# sensor_de_linha.net
KiCad netlist of a schematic drawn in EAGLE
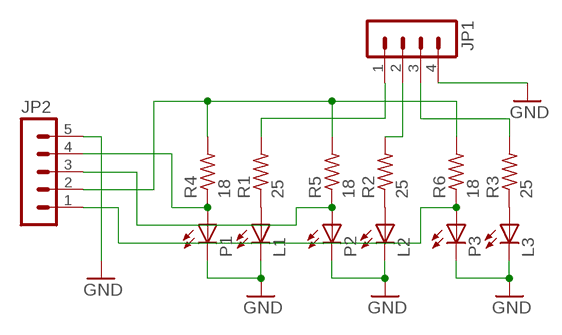
[diagram p0: schematic, sheet 1]

(export (version "E")
  (design (tool "Eeschema 10.0.6"))
  (components
    (comp (ref "JP1")
      (value "MA04-1")
      (footprint "eagle-import:MA04-1")
      (libsource (lib "eagle-import") (part "MA04-1"))
    )
    (comp (ref "JP2")
      (value "MA05-1")
      (footprint "eagle-import:MA05-1")
      (fields (field (name "OC_FARNELL") "unknown") (field (name "OC_NEWARK") "unknown"))
      (libsource (lib "eagle-import") (part "MA05-1"))
    )
    (comp (ref "L1")
      (value "LED3MM")
      (footprint "eagle-import:LED3MM")
      (libsource (lib "eagle-import") (part "LED3MM"))
    )
    (comp (ref "L2")
      (value "LED3MM")
      (footprint "eagle-import:LED3MM")
      (libsource (lib "eagle-import") (part "LED3MM"))
    )
    (comp (ref "L3")
      (value "LED3MM")
      (footprint "eagle-import:LED3MM")
      (libsource (lib "eagle-import") (part "LED3MM"))
    )
    (comp (ref "P1")
      (value "LED3MM")
      (footprint "eagle-import:LED3MM")
      (libsource (lib "eagle-import") (part "LED3MM"))
    )
    (comp (ref "P2")
      (value "LED3MM")
      (footprint "eagle-import:LED3MM")
      (libsource (lib "eagle-import") (part "LED3MM"))
    )
    (comp (ref "P3")
      (value "LED3MM")
      (footprint "eagle-import:LED3MM")
      (libsource (lib "eagle-import") (part "LED3MM"))
    )
    (comp (ref "R1")
      (value "25")
      (footprint "eagle-import:R0805")
      (libsource (lib "eagle-import") (part "R-US_R0805"))
    )
    (comp (ref "R2")
      (value "25")
      (footprint "eagle-import:R0805")
      (libsource (lib "eagle-import") (part "R-US_R0805"))
    )
    (comp (ref "R3")
      (value "25")
      (footprint "eagle-import:R0805")
      (libsource (lib "eagle-import") (part "R-US_R0805"))
    )
    (comp (ref "R4")
      (value "18")
      (footprint "eagle-import:R0805")
      (libsource (lib "eagle-import") (part "R-US_R0805"))
    )
    (comp (ref "R5")
      (value "18")
      (footprint "eagle-import:R0805")
      (libsource (lib "eagle-import") (part "R-US_R0805"))
    )
    (comp (ref "R6")
      (value "18")
      (footprint "eagle-import:R0805")
      (libsource (lib "eagle-import") (part "R-US_R0805"))
    )
  )
  (nets
    (net (code "1") (name "GND") (class "Default")
      (node (ref "JP1") (pin "4") (pinfunction "4_4") (pintype "passive"))
      (node (ref "JP2") (pin "5") (pinfunction "5_5") (pintype "passive"))
      (node (ref "L1") (pin "K") (pinfunction "C_K") (pintype "passive"))
      (node (ref "L2") (pin "K") (pinfunction "C_K") (pintype "passive"))
      (node (ref "L3") (pin "K") (pinfunction "C_K") (pintype "passive"))
      (node (ref "P1") (pin "K") (pinfunction "C_K") (pintype "passive"))
      (node (ref "P2") (pin "K") (pinfunction "C_K") (pintype "passive"))
      (node (ref "P3") (pin "K") (pinfunction "C_K") (pintype "passive"))
    )
    (net (code "2") (name "Net-(JP1-Pad1)") (class "Default")
      (node (ref "JP1") (pin "1") (pinfunction "1_1") (pintype "passive"))
      (node (ref "R1") (pin "2") (pinfunction "2_2") (pintype "passive"))
    )
    (net (code "3") (name "Net-(JP1-Pad2)") (class "Default")
      (node (ref "JP1") (pin "2") (pinfunction "2_2") (pintype "passive"))
      (node (ref "R2") (pin "2") (pinfunction "2_2") (pintype "passive"))
    )
    (net (code "4") (name "Net-(JP1-Pad3)") (class "Default")
      (node (ref "JP1") (pin "3") (pinfunction "3_3") (pintype "passive"))
      (node (ref "R3") (pin "2") (pinfunction "2_2") (pintype "passive"))
    )
    (net (code "5") (name "Net-(JP2-Pad1)") (class "Default")
      (node (ref "JP2") (pin "1") (pinfunction "1_1") (pintype "passive"))
      (node (ref "P3") (pin "A") (pinfunction "A_A") (pintype "passive"))
      (node (ref "R6") (pin "1") (pinfunction "1_1") (pintype "passive"))
    )
    (net (code "6") (name "Net-(JP2-Pad2)") (class "Default")
      (node (ref "JP2") (pin "2") (pinfunction "2_2") (pintype "passive"))
      (node (ref "R4") (pin "2") (pinfunction "2_2") (pintype "passive"))
      (node (ref "R5") (pin "2") (pinfunction "2_2") (pintype "passive"))
      (node (ref "R6") (pin "2") (pinfunction "2_2") (pintype "passive"))
    )
    (net (code "7") (name "Net-(JP2-Pad3)") (class "Default")
      (node (ref "JP2") (pin "3") (pinfunction "3_3") (pintype "passive"))
      (node (ref "P2") (pin "A") (pinfunction "A_A") (pintype "passive"))
      (node (ref "R5") (pin "1") (pinfunction "1_1") (pintype "passive"))
    )
    (net (code "8") (name "Net-(JP2-Pad4)") (class "Default")
      (node (ref "JP2") (pin "4") (pinfunction "4_4") (pintype "passive"))
      (node (ref "P1") (pin "A") (pinfunction "A_A") (pintype "passive"))
      (node (ref "R4") (pin "1") (pinfunction "1_1") (pintype "passive"))
    )
    (net (code "9") (name "Net-(L1-PadA)") (class "Default")
      (node (ref "L1") (pin "A") (pinfunction "A_A") (pintype "passive"))
      (node (ref "R1") (pin "1") (pinfunction "1_1") (pintype "passive"))
    )
    (net (code "10") (name "Net-(L2-PadA)") (class "Default")
      (node (ref "L2") (pin "A") (pinfunction "A_A") (pintype "passive"))
      (node (ref "R2") (pin "1") (pinfunction "1_1") (pintype "passive"))
    )
    (net (code "11") (name "Net-(L3-PadA)") (class "Default")
      (node (ref "L3") (pin "A") (pinfunction "A_A") (pintype "passive"))
      (node (ref "R3") (pin "1") (pinfunction "1_1") (pintype "passive"))
    )
  )
)
